# 02A-007_Input_Switch.net
KiCad netlist of a schematic drawn in EAGLE
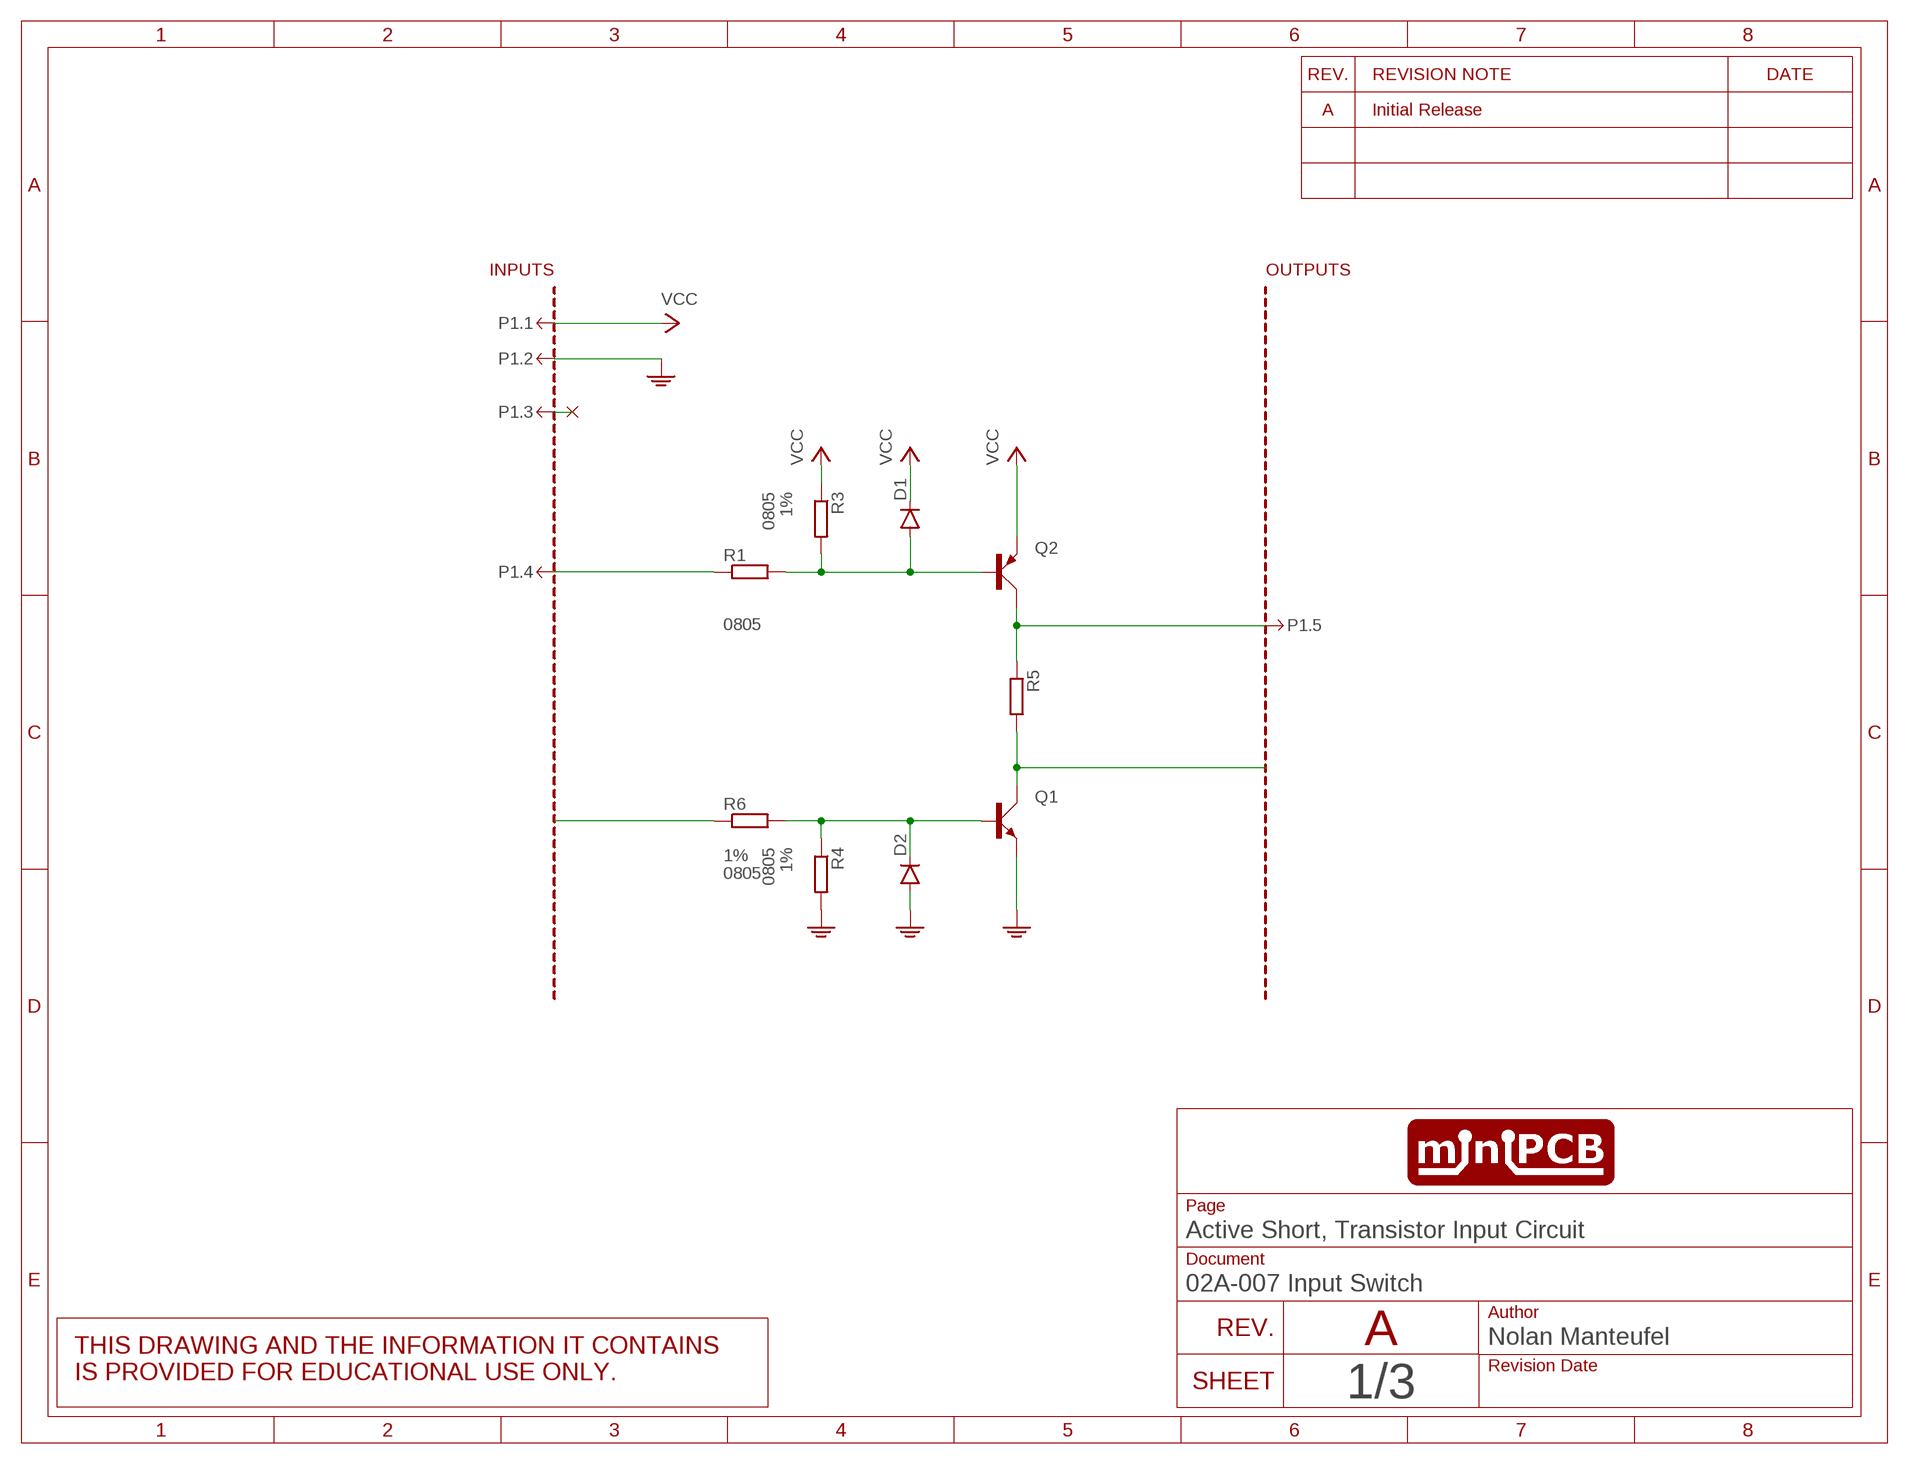
[diagram p0: schematic, sheet 1]
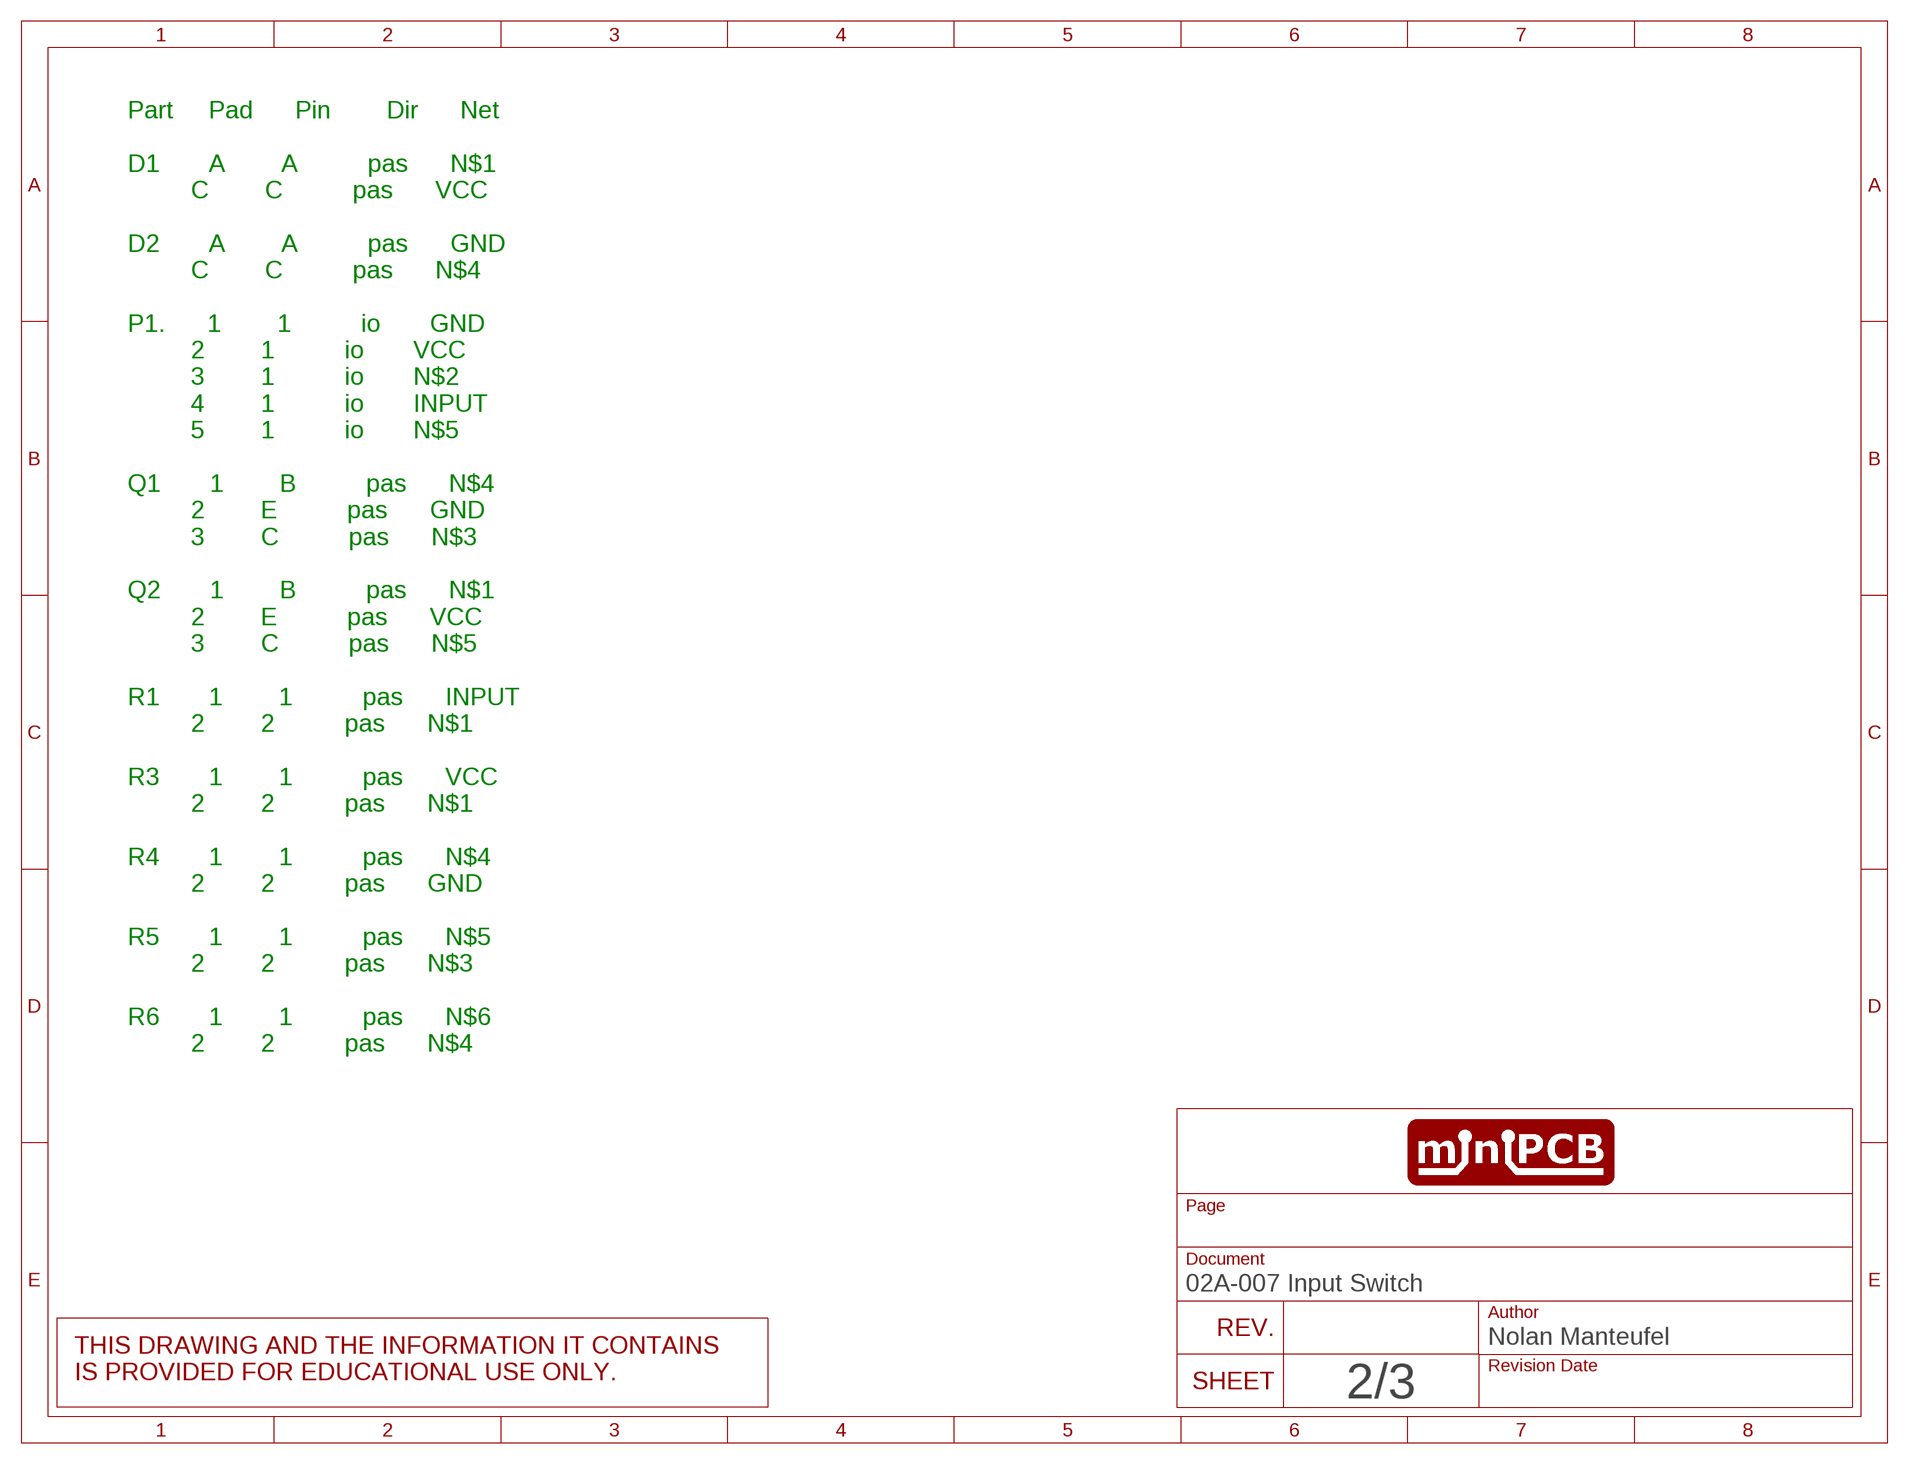
[diagram p1: schematic, sheet 2]
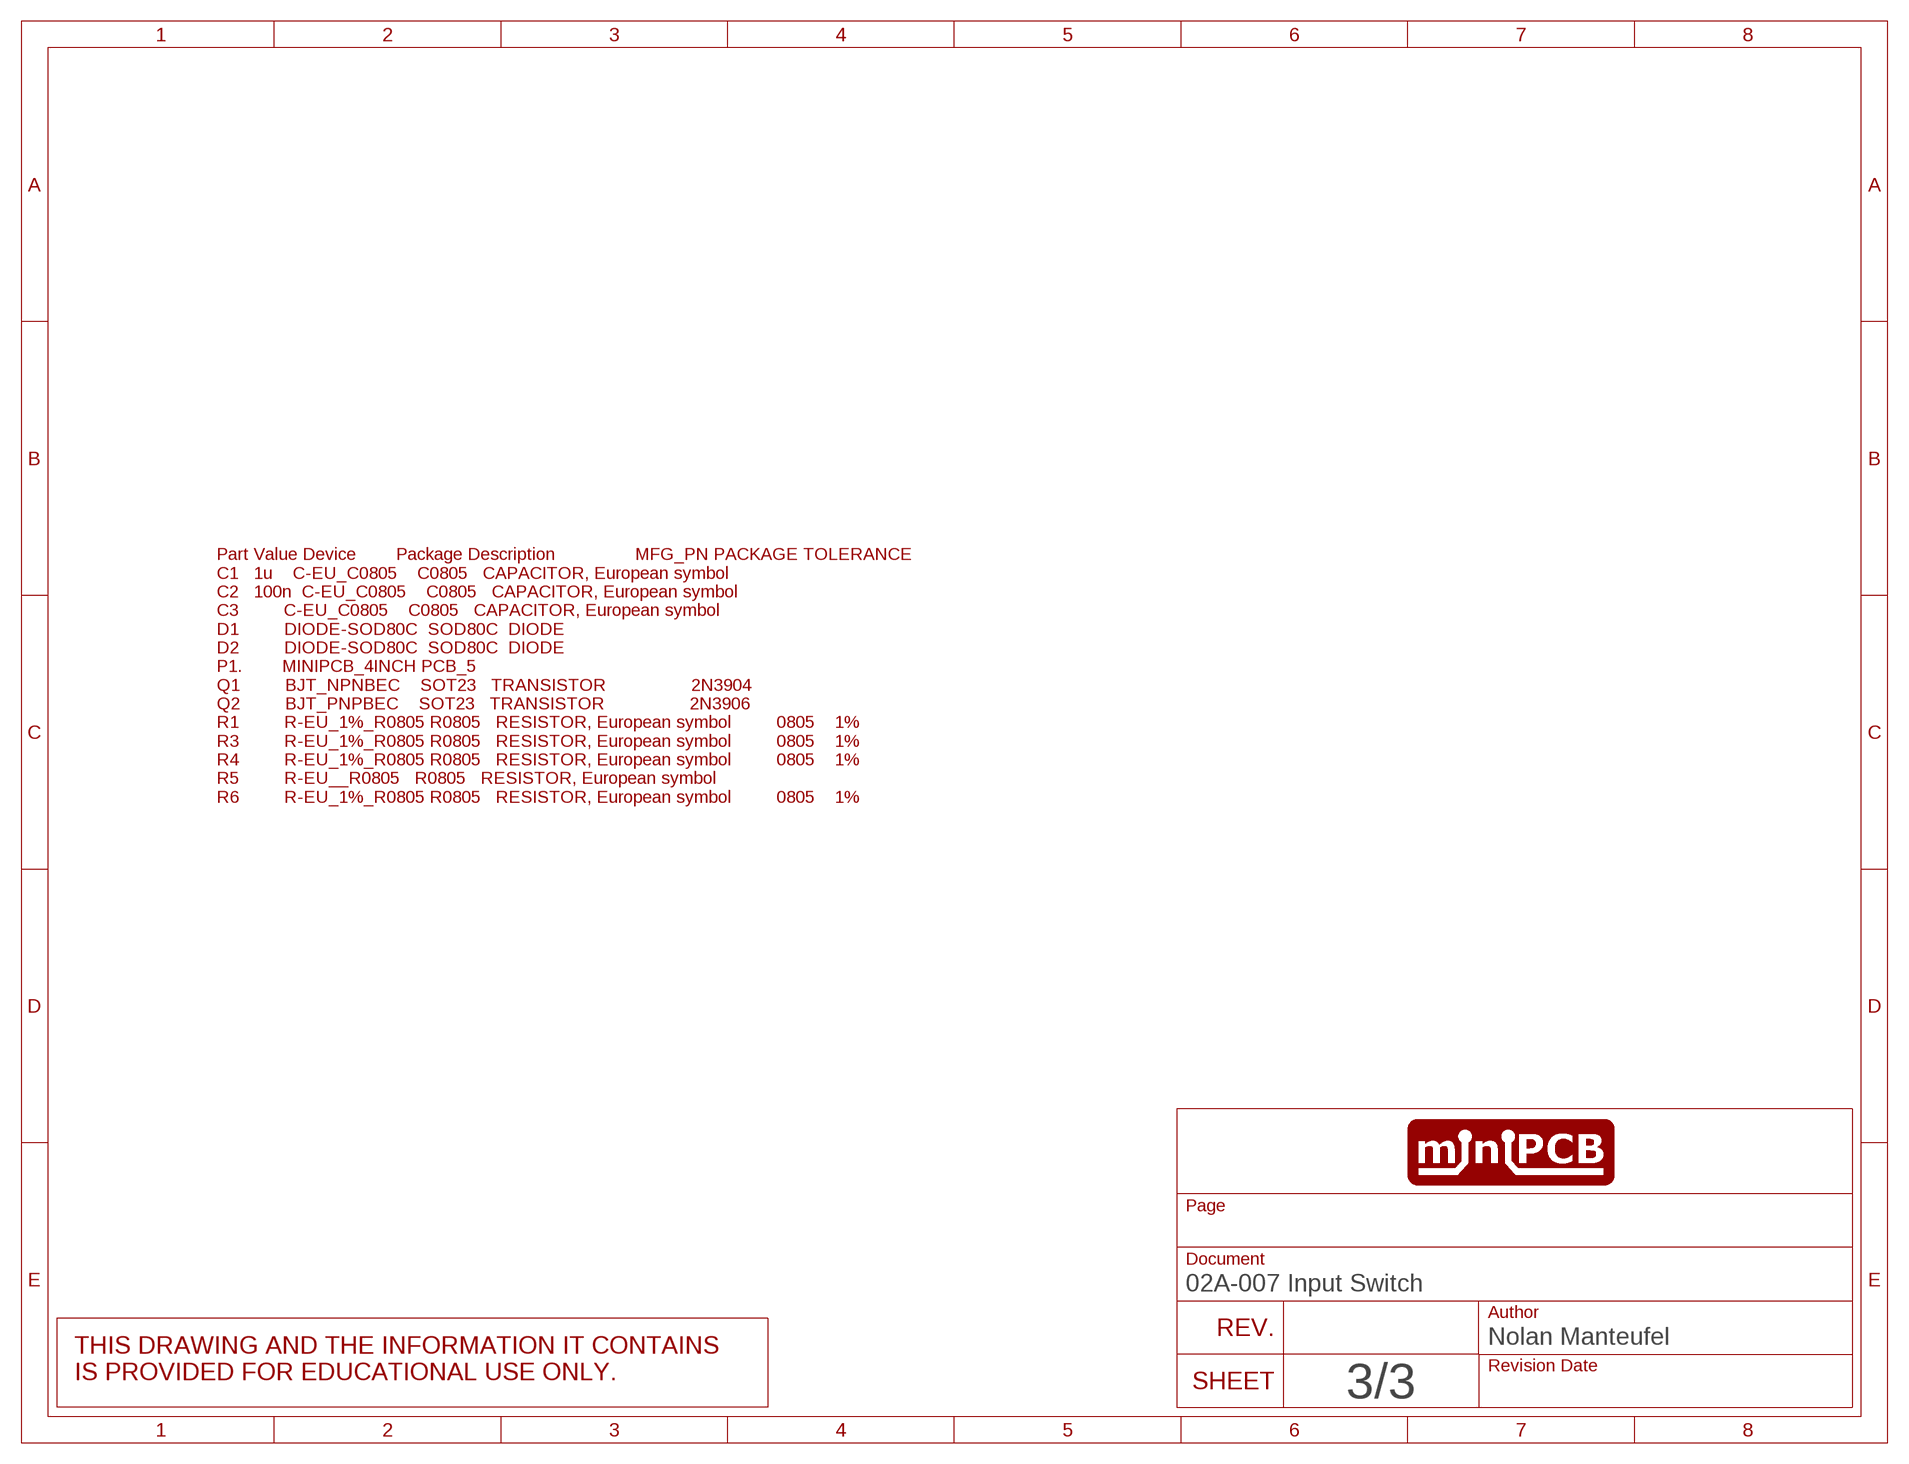
[diagram p2: schematic, sheet 3]

(export (version "E")
  (design (tool "Eeschema 10.0.6"))
  (components
    (comp (ref "D1")
      (value "DIODE-SOD80C")
      (footprint "eagle-import:SOD80C")
      (libsource (lib "eagle-import") (part "DIODE-SOD80C"))
    )
    (comp (ref "D2")
      (value "DIODE-SOD80C")
      (footprint "eagle-import:SOD80C")
      (libsource (lib "eagle-import") (part "DIODE-SOD80C"))
    )
    (comp (ref "P1.")
      (value "MINIPCB_4INCH")
      (footprint "eagle-import:PCB_5")
      (libsource (lib "eagle-import") (part "MINIPCB_4INCH"))
    )
    (comp (ref "Q1")
      (value "BJT_NPNBEC")
      (footprint "eagle-import:SOT23")
      (fields (field (name "MFG_PN") "2N3904"))
      (libsource (lib "eagle-import") (part "BJT_NPNBEC"))
    )
    (comp (ref "Q2")
      (value "BJT_PNPBEC")
      (footprint "eagle-import:SOT23")
      (fields (field (name "MFG_PN") "2N3906"))
      (libsource (lib "eagle-import") (part "BJT_PNPBEC"))
    )
    (comp (ref "R1")
      (value "R-EU_1%_R0805")
      (footprint "eagle-import:R0805")
      (fields (field (name "TOLERANCE") "1%") (field (name "TOLERANCE_1") "1%"))
      (libsource (lib "eagle-import") (part "R-EU__R08051%"))
    )
    (comp (ref "R3")
      (value "R-EU_1%_R0805")
      (footprint "eagle-import:R0805")
      (fields (field (name "TOLERANCE") "1%"))
      (libsource (lib "eagle-import") (part "R-EU__R08051%"))
    )
    (comp (ref "R4")
      (value "R-EU_1%_R0805")
      (footprint "eagle-import:R0805")
      (fields (field (name "TOLERANCE") "1%") (field (name "TOLERANCE_1") "1%"))
      (libsource (lib "eagle-import") (part "R-EU__R08051%"))
    )
    (comp (ref "R5")
      (value "R-EU__R0805")
      (footprint "eagle-import:R0805")
      (libsource (lib "eagle-import") (part "R-EU__R0805"))
    )
    (comp (ref "R6")
      (value "R-EU_1%_R0805")
      (footprint "eagle-import:R0805")
      (fields (field (name "TOLERANCE") "1%") (field (name "TOLERANCE_1") "1%"))
      (libsource (lib "eagle-import") (part "R-EU__R08051%"))
    )
  )
  (nets
    (net (code "1") (name "GND") (class "Default")
      (node (ref "D2") (pin "A") (pinfunction "A_A") (pintype "passive"))
      (node (ref "P1.") (pin "1") (pinfunction "1_1") (pintype "bidirectional"))
      (node (ref "Q1") (pin "2") (pinfunction "E_2") (pintype "passive"))
      (node (ref "R4") (pin "2") (pinfunction "2_2") (pintype "passive"))
    )
    (net (code "2") (name "Net-(P1.D-1)") (class "Default")
      (node (ref "P1.") (pin "4") (pinfunction "1_4") (pintype "bidirectional"))
      (node (ref "R1") (pin "1") (pinfunction "1_1") (pintype "passive"))
    )
    (net (code "3") (name "Net-(P1.H-1)") (class "Default")
      (node (ref "P1.") (pin "5") (pinfunction "1_5") (pintype "bidirectional"))
      (node (ref "Q2") (pin "3") (pinfunction "C_3") (pintype "passive"))
      (node (ref "R5") (pin "1") (pinfunction "1_1") (pintype "passive"))
    )
    (net (code "4") (name "Net-(Q1-B)") (class "Default")
      (node (ref "D2") (pin "C") (pinfunction "C_C") (pintype "passive"))
      (node (ref "Q1") (pin "1") (pinfunction "B_1") (pintype "passive"))
      (node (ref "R4") (pin "1") (pinfunction "1_1") (pintype "passive"))
      (node (ref "R6") (pin "2") (pinfunction "2_2") (pintype "passive"))
    )
    (net (code "5") (name "Net-(Q1-C)") (class "Default")
      (node (ref "Q1") (pin "3") (pinfunction "C_3") (pintype "passive"))
      (node (ref "R5") (pin "2") (pinfunction "2_2") (pintype "passive"))
    )
    (net (code "6") (name "Net-(Q2-B)") (class "Default")
      (node (ref "D1") (pin "A") (pinfunction "A_A") (pintype "passive"))
      (node (ref "Q2") (pin "1") (pinfunction "B_1") (pintype "passive"))
      (node (ref "R1") (pin "2") (pinfunction "2_2") (pintype "passive"))
      (node (ref "R3") (pin "2") (pinfunction "2_2") (pintype "passive"))
    )
    (net (code "7") (name "VCC") (class "Default")
      (node (ref "D1") (pin "C") (pinfunction "C_C") (pintype "passive"))
      (node (ref "P1.") (pin "2") (pinfunction "1_2") (pintype "bidirectional"))
      (node (ref "Q2") (pin "2") (pinfunction "E_2") (pintype "passive"))
      (node (ref "R3") (pin "1") (pinfunction "1_1") (pintype "passive"))
    )
    (net (code "8") (name "unconnected-(P1.C-1-Pad3)") (class "Default")
      (node (ref "P1.") (pin "3") (pinfunction "1_3") (pintype "bidirectional"))
    )
    (net (code "9") (name "unconnected-(R6-Pad1)") (class "Default")
      (node (ref "R6") (pin "1") (pinfunction "1_1") (pintype "passive"))
    )
  )
)
